# ups-node.net
KiCad netlist of a schematic drawn in EAGLE
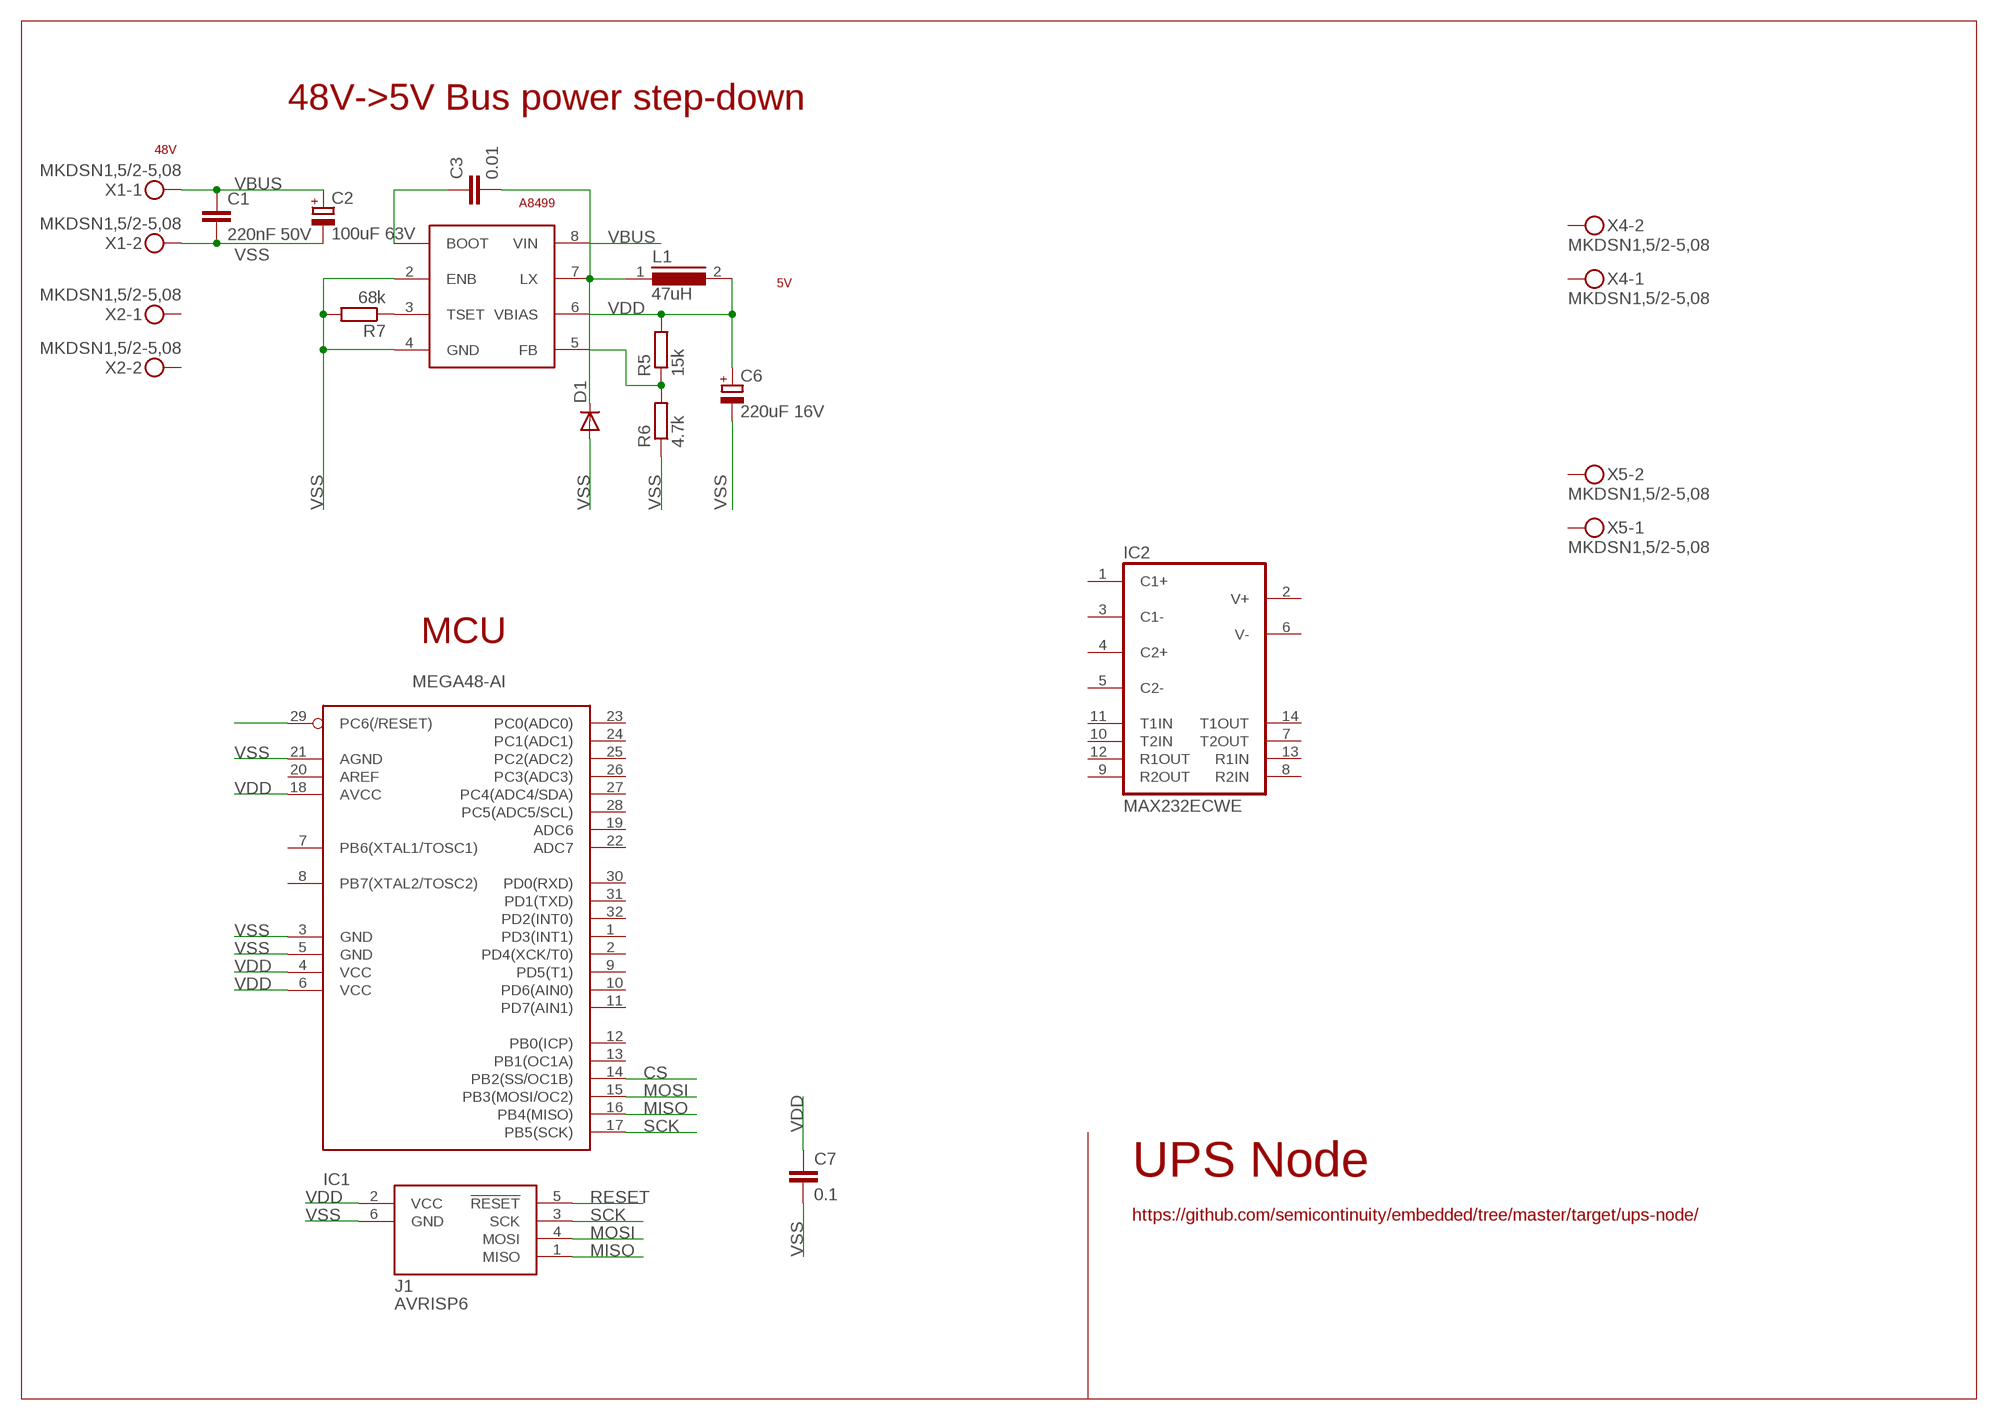
[diagram p0: schematic, sheet 1]

(export (version "E")
  (design (tool "Eeschema 10.0.6"))
  (components
    (comp (ref "C1")
      (value "220nF 50V")
      (footprint "eagle-import:C0805")
      (libsource (lib "eagle-import") (part "C-EUC0805"))
    )
    (comp (ref "C2")
      (value "100uF 63V")
      (footprint "eagle-import:153CLV-1010")
      (libsource (lib "eagle-import") (part "CPOL-EU153CLV-1010"))
    )
    (comp (ref "C3")
      (value "0.01")
      (footprint "eagle-import:C0805")
      (libsource (lib "eagle-import") (part "C-EUC0805"))
    )
    (comp (ref "C6")
      (value "220uF 16V")
      (footprint "eagle-import:153CLV-0605")
      (libsource (lib "eagle-import") (part "CPOL-EU153CLV-0605"))
    )
    (comp (ref "C7")
      (value "0.1")
      (footprint "eagle-import:C0805")
      (libsource (lib "eagle-import") (part "C-EUC0805"))
    )
    (comp (ref "D1")
      (value "DIODE-SMB")
      (footprint "eagle-import:SMB")
      (libsource (lib "eagle-import") (part "DIODE-SMB"))
    )
    (comp (ref "IC1")
      (value "MEGA48-AI")
      (footprint "eagle-import:TQFP32-08")
      (libsource (lib "eagle-import") (part "MEGA8-AI"))
    )
    (comp (ref "IC2")
      (value "MAX232ECWE")
      (footprint "eagle-import:SO16L")
      (fields (field (name "MF") "MAXIM") (field (name "MPN") "MAX232ECWE+"))
      (libsource (lib "eagle-import") (part "MAX232ECWE"))
    )
    (comp (ref "J1")
      (value "AVRISP6")
      (footprint "eagle-import:CON6P2R")
      (libsource (lib "eagle-import") (part "AVRISP6"))
    )
    (comp (ref "L1")
      (value "47uH")
      (footprint "eagle-import:DR127")
      (libsource (lib "eagle-import") (part "DR127"))
    )
    (comp (ref "R5")
      (value "15k")
      (footprint "eagle-import:R0805")
      (libsource (lib "eagle-import") (part "R-EU_R0805"))
    )
    (comp (ref "R6")
      (value "4.7k")
      (footprint "eagle-import:R0805")
      (libsource (lib "eagle-import") (part "R-EU_R0805"))
    )
    (comp (ref "R7")
      (value "68k")
      (footprint "eagle-import:R0805")
      (libsource (lib "eagle-import") (part "R-EU_R0805"))
    )
    (comp (ref "U$1")
      (value "A8499")
      (footprint "eagle-import:SO08")
      (libsource (lib "eagle-import") (part "A8499SLJT"))
    )
    (comp (ref "X1")
      (value "MKDSN1,5/2-5,08")
      (footprint "eagle-import:MKDSN1,5_2-5,08")
      (fields (field (name "MPN") "MKDSN 1,5/2-5.08"))
      (libsource (lib "eagle-import") (part "MKDSN1,5/2-5,08"))
    )
    (comp (ref "X2")
      (value "MKDSN1,5/2-5,08")
      (footprint "eagle-import:MKDSN1,5_2-5,08")
      (fields (field (name "MPN") "MKDSN 1,5/2-5.08"))
      (libsource (lib "eagle-import") (part "MKDSN1,5/2-5,08"))
    )
    (comp (ref "X4")
      (value "MKDSN1,5/2-5,08")
      (footprint "eagle-import:MKDSN1,5_2-5,08")
      (fields (field (name "MPN") "MKDSN 1,5/2-5.08"))
      (libsource (lib "eagle-import") (part "MKDSN1,5/2-5,08"))
    )
    (comp (ref "X5")
      (value "MKDSN1,5/2-5,08")
      (footprint "eagle-import:MKDSN1,5_2-5,08")
      (fields (field (name "MPN") "MKDSN 1,5/2-5.08"))
      (libsource (lib "eagle-import") (part "MKDSN1,5/2-5,08"))
    )
  )
  (nets
    (net (code "1") (name "/CS") (class "Default")
      (node (ref "IC1") (pin "14") (pinfunction "PB2(SS/OC1B)_14") (pintype "bidirectional"))
    )
    (net (code "2") (name "/MISO") (class "Default")
      (node (ref "IC1") (pin "16") (pinfunction "PB4(MISO)_16") (pintype "bidirectional"))
      (node (ref "J1") (pin "1") (pinfunction "MISO_1") (pintype "input"))
    )
    (net (code "3") (name "/MOSI") (class "Default")
      (node (ref "IC1") (pin "15") (pinfunction "PB3(MOSI/OC2)_15") (pintype "bidirectional"))
      (node (ref "J1") (pin "4") (pinfunction "MOSI_4") (pintype "output"))
    )
    (net (code "4") (name "/RESET") (class "Default")
      (node (ref "IC1") (pin "29") (pinfunction "PC6(/RESET)_29") (pintype "bidirectional"))
      (node (ref "J1") (pin "5") (pinfunction "~{RESET}_5") (pintype "output"))
    )
    (net (code "5") (name "/SCK") (class "Default")
      (node (ref "IC1") (pin "17") (pinfunction "PB5(SCK)_17") (pintype "bidirectional"))
      (node (ref "J1") (pin "3") (pinfunction "SCK_3") (pintype "output"))
    )
    (net (code "6") (name "/VBUS") (class "Default")
      (node (ref "C1") (pin "1") (pinfunction "1_1") (pintype "passive"))
      (node (ref "C2") (pin "+") (pinfunction "+_+") (pintype "passive"))
      (node (ref "U$1") (pin "8") (pinfunction "VIN_8") (pintype "power_in"))
      (node (ref "X1") (pin "1") (pinfunction "KL_1") (pintype "passive"))
    )
    (net (code "7") (name "/VDD") (class "Default")
      (node (ref "C6") (pin "+") (pinfunction "+_+") (pintype "passive"))
      (node (ref "C7") (pin "1") (pinfunction "1_1") (pintype "passive"))
      (node (ref "IC1") (pin "18") (pinfunction "AVCC_18") (pintype "bidirectional"))
      (node (ref "IC1") (pin "4") (pinfunction "VCC_4") (pintype "bidirectional"))
      (node (ref "IC1") (pin "6") (pinfunction "VCC_6") (pintype "bidirectional"))
      (node (ref "J1") (pin "2") (pinfunction "VCC_2") (pintype "power_in"))
      (node (ref "L1") (pin "2") (pinfunction "2_2") (pintype "passive"))
      (node (ref "R5") (pin "2") (pinfunction "2_2") (pintype "passive"))
      (node (ref "U$1") (pin "6") (pinfunction "VBIAS_6") (pintype "power_in"))
    )
    (net (code "8") (name "/VSS") (class "Default")
      (node (ref "C1") (pin "2") (pinfunction "2_2") (pintype "passive"))
      (node (ref "C2") (pin "-") (pinfunction "-_-") (pintype "passive"))
      (node (ref "C6") (pin "-") (pinfunction "-_-") (pintype "passive"))
      (node (ref "C7") (pin "2") (pinfunction "2_2") (pintype "passive"))
      (node (ref "D1") (pin "A") (pinfunction "A_A") (pintype "passive"))
      (node (ref "IC1") (pin "21") (pinfunction "AGND_21") (pintype "bidirectional"))
      (node (ref "IC1") (pin "3") (pinfunction "GND_3") (pintype "bidirectional"))
      (node (ref "IC1") (pin "5") (pinfunction "GND_5") (pintype "bidirectional"))
      (node (ref "J1") (pin "6") (pinfunction "GND_6") (pintype "power_in"))
      (node (ref "R6") (pin "1") (pinfunction "1_1") (pintype "passive"))
      (node (ref "R7") (pin "2") (pinfunction "2_2") (pintype "passive"))
      (node (ref "U$1") (pin "2") (pinfunction "ENB_2") (pintype "power_in"))
      (node (ref "U$1") (pin "4") (pinfunction "GND_4") (pintype "power_in"))
      (node (ref "X1") (pin "2") (pinfunction "KL_2") (pintype "passive"))
    )
    (net (code "9") (name "Net-(U$1-BOOT)") (class "Default")
      (node (ref "C3") (pin "1") (pinfunction "1_1") (pintype "passive"))
      (node (ref "U$1") (pin "1") (pinfunction "BOOT_1") (pintype "power_in"))
    )
    (net (code "10") (name "Net-(U$1-FB)") (class "Default")
      (node (ref "R5") (pin "1") (pinfunction "1_1") (pintype "passive"))
      (node (ref "R6") (pin "2") (pinfunction "2_2") (pintype "passive"))
      (node (ref "U$1") (pin "5") (pinfunction "FB_5") (pintype "power_in"))
    )
    (net (code "11") (name "Net-(U$1-LX)") (class "Default")
      (node (ref "C3") (pin "2") (pinfunction "2_2") (pintype "passive"))
      (node (ref "D1") (pin "C") (pinfunction "C_C") (pintype "passive"))
      (node (ref "L1") (pin "1") (pinfunction "1_1") (pintype "passive"))
      (node (ref "U$1") (pin "7") (pinfunction "LX_7") (pintype "power_in"))
    )
    (net (code "12") (name "Net-(U$1-TSET)") (class "Default")
      (node (ref "R7") (pin "1") (pinfunction "1_1") (pintype "passive"))
      (node (ref "U$1") (pin "3") (pinfunction "TSET_3") (pintype "power_in"))
    )
    (net (code "13") (name "unconnected-(IC1-ADC6-Pad19)") (class "Default")
      (node (ref "IC1") (pin "19") (pinfunction "ADC6_19") (pintype "bidirectional"))
    )
    (net (code "14") (name "unconnected-(IC1-ADC7-Pad22)") (class "Default")
      (node (ref "IC1") (pin "22") (pinfunction "ADC7_22") (pintype "bidirectional"))
    )
    (net (code "15") (name "unconnected-(IC1-AREF-Pad20)") (class "Default")
      (node (ref "IC1") (pin "20") (pinfunction "AREF_20") (pintype "bidirectional"))
    )
    (net (code "16") (name "unconnected-(IC1-PB0(ICP)-Pad12)") (class "Default")
      (node (ref "IC1") (pin "12") (pinfunction "PB0(ICP)_12") (pintype "bidirectional"))
    )
    (net (code "17") (name "unconnected-(IC1-PB1(OC1A)-Pad13)") (class "Default")
      (node (ref "IC1") (pin "13") (pinfunction "PB1(OC1A)_13") (pintype "bidirectional"))
    )
    (net (code "18") (name "unconnected-(IC1-PB6(XTAL1{slash}TOSC1)-Pad7)") (class "Default")
      (node (ref "IC1") (pin "7") (pinfunction "PB6(XTAL1/TOSC1)_7") (pintype "bidirectional"))
    )
    (net (code "19") (name "unconnected-(IC1-PB7(XTAL2{slash}TOSC2)-Pad8)") (class "Default")
      (node (ref "IC1") (pin "8") (pinfunction "PB7(XTAL2/TOSC2)_8") (pintype "bidirectional"))
    )
    (net (code "20") (name "unconnected-(IC1-PC0(ADC0)-Pad23)") (class "Default")
      (node (ref "IC1") (pin "23") (pinfunction "PC0(ADC0)_23") (pintype "bidirectional"))
    )
    (net (code "21") (name "unconnected-(IC1-PC1(ADC1)-Pad24)") (class "Default")
      (node (ref "IC1") (pin "24") (pinfunction "PC1(ADC1)_24") (pintype "bidirectional"))
    )
    (net (code "22") (name "unconnected-(IC1-PC2(ADC2)-Pad25)") (class "Default")
      (node (ref "IC1") (pin "25") (pinfunction "PC2(ADC2)_25") (pintype "bidirectional"))
    )
    (net (code "23") (name "unconnected-(IC1-PC3(ADC3)-Pad26)") (class "Default")
      (node (ref "IC1") (pin "26") (pinfunction "PC3(ADC3)_26") (pintype "bidirectional"))
    )
    (net (code "24") (name "unconnected-(IC1-PC4(ADC4{slash}SDA)-Pad27)") (class "Default")
      (node (ref "IC1") (pin "27") (pinfunction "PC4(ADC4/SDA)_27") (pintype "bidirectional"))
    )
    (net (code "25") (name "unconnected-(IC1-PC5(ADC5{slash}SCL)-Pad28)") (class "Default")
      (node (ref "IC1") (pin "28") (pinfunction "PC5(ADC5/SCL)_28") (pintype "bidirectional"))
    )
    (net (code "26") (name "unconnected-(IC1-PD0(RXD)-Pad30)") (class "Default")
      (node (ref "IC1") (pin "30") (pinfunction "PD0(RXD)_30") (pintype "bidirectional"))
    )
    (net (code "27") (name "unconnected-(IC1-PD1(TXD)-Pad31)") (class "Default")
      (node (ref "IC1") (pin "31") (pinfunction "PD1(TXD)_31") (pintype "bidirectional"))
    )
    (net (code "28") (name "unconnected-(IC1-PD2(INT0)-Pad32)") (class "Default")
      (node (ref "IC1") (pin "32") (pinfunction "PD2(INT0)_32") (pintype "bidirectional"))
    )
    (net (code "29") (name "unconnected-(IC1-PD3(INT1)-Pad1)") (class "Default")
      (node (ref "IC1") (pin "1") (pinfunction "PD3(INT1)_1") (pintype "bidirectional"))
    )
    (net (code "30") (name "unconnected-(IC1-PD4(XCK{slash}T0)-Pad2)") (class "Default")
      (node (ref "IC1") (pin "2") (pinfunction "PD4(XCK/T0)_2") (pintype "bidirectional"))
    )
    (net (code "31") (name "unconnected-(IC1-PD5(T1)-Pad9)") (class "Default")
      (node (ref "IC1") (pin "9") (pinfunction "PD5(T1)_9") (pintype "bidirectional"))
    )
    (net (code "32") (name "unconnected-(IC1-PD6(AIN0)-Pad10)") (class "Default")
      (node (ref "IC1") (pin "10") (pinfunction "PD6(AIN0)_10") (pintype "bidirectional"))
    )
    (net (code "33") (name "unconnected-(IC1-PD7(AIN1)-Pad11)") (class "Default")
      (node (ref "IC1") (pin "11") (pinfunction "PD7(AIN1)_11") (pintype "bidirectional"))
    )
    (net (code "34") (name "unconnected-(IC2A-C1+-Pad1)") (class "Default")
      (node (ref "IC2") (pin "1") (pinfunction "C1+_1") (pintype "bidirectional"))
    )
    (net (code "35") (name "unconnected-(IC2A-C1--Pad3)") (class "Default")
      (node (ref "IC2") (pin "3") (pinfunction "C1-_3") (pintype "bidirectional"))
    )
    (net (code "36") (name "unconnected-(IC2A-C2+-Pad4)") (class "Default")
      (node (ref "IC2") (pin "4") (pinfunction "C2+_4") (pintype "bidirectional"))
    )
    (net (code "37") (name "unconnected-(IC2A-C2--Pad5)") (class "Default")
      (node (ref "IC2") (pin "5") (pinfunction "C2-_5") (pintype "bidirectional"))
    )
    (net (code "38") (name "unconnected-(IC2A-R1IN-Pad13)") (class "Default")
      (node (ref "IC2") (pin "13") (pinfunction "R1IN_13") (pintype "input"))
    )
    (net (code "39") (name "unconnected-(IC2A-R1OUT-Pad12)") (class "Default")
      (node (ref "IC2") (pin "12") (pinfunction "R1OUT_12") (pintype "output"))
    )
    (net (code "40") (name "unconnected-(IC2A-R2IN-Pad8)") (class "Default")
      (node (ref "IC2") (pin "8") (pinfunction "R2IN_8") (pintype "input"))
    )
    (net (code "41") (name "unconnected-(IC2A-R2OUT-Pad9)") (class "Default")
      (node (ref "IC2") (pin "9") (pinfunction "R2OUT_9") (pintype "output"))
    )
    (net (code "42") (name "unconnected-(IC2A-T1IN-Pad11)") (class "Default")
      (node (ref "IC2") (pin "11") (pinfunction "T1IN_11") (pintype "input"))
    )
    (net (code "43") (name "unconnected-(IC2A-T1OUT-Pad14)") (class "Default")
      (node (ref "IC2") (pin "14") (pinfunction "T1OUT_14") (pintype "output"))
    )
    (net (code "44") (name "unconnected-(IC2A-T2IN-Pad10)") (class "Default")
      (node (ref "IC2") (pin "10") (pinfunction "T2IN_10") (pintype "input"))
    )
    (net (code "45") (name "unconnected-(IC2A-T2OUT-Pad7)") (class "Default")
      (node (ref "IC2") (pin "7") (pinfunction "T2OUT_7") (pintype "output"))
    )
    (net (code "46") (name "unconnected-(IC2A-V+-Pad2)") (class "Default")
      (node (ref "IC2") (pin "2") (pinfunction "V+_2") (pintype "bidirectional"))
    )
    (net (code "47") (name "unconnected-(IC2A-V--Pad6)") (class "Default")
      (node (ref "IC2") (pin "6") (pinfunction "V-_6") (pintype "bidirectional"))
    )
    (net (code "48") (name "unconnected-(X2A-KL-Pad1)") (class "Default")
      (node (ref "X2") (pin "1") (pinfunction "KL_1") (pintype "passive"))
    )
    (net (code "49") (name "unconnected-(X2B-KL-Pad2)") (class "Default")
      (node (ref "X2") (pin "2") (pinfunction "KL_2") (pintype "passive"))
    )
    (net (code "50") (name "unconnected-(X4A-KL-Pad1)") (class "Default")
      (node (ref "X4") (pin "1") (pinfunction "KL_1") (pintype "passive"))
    )
    (net (code "51") (name "unconnected-(X4B-KL-Pad2)") (class "Default")
      (node (ref "X4") (pin "2") (pinfunction "KL_2") (pintype "passive"))
    )
    (net (code "52") (name "unconnected-(X5A-KL-Pad1)") (class "Default")
      (node (ref "X5") (pin "1") (pinfunction "KL_1") (pintype "passive"))
    )
    (net (code "53") (name "unconnected-(X5B-KL-Pad2)") (class "Default")
      (node (ref "X5") (pin "2") (pinfunction "KL_2") (pintype "passive"))
    )
  )
)
